# DAC_and_MIC.net
KiCad netlist of a schematic drawn in Altium Designer
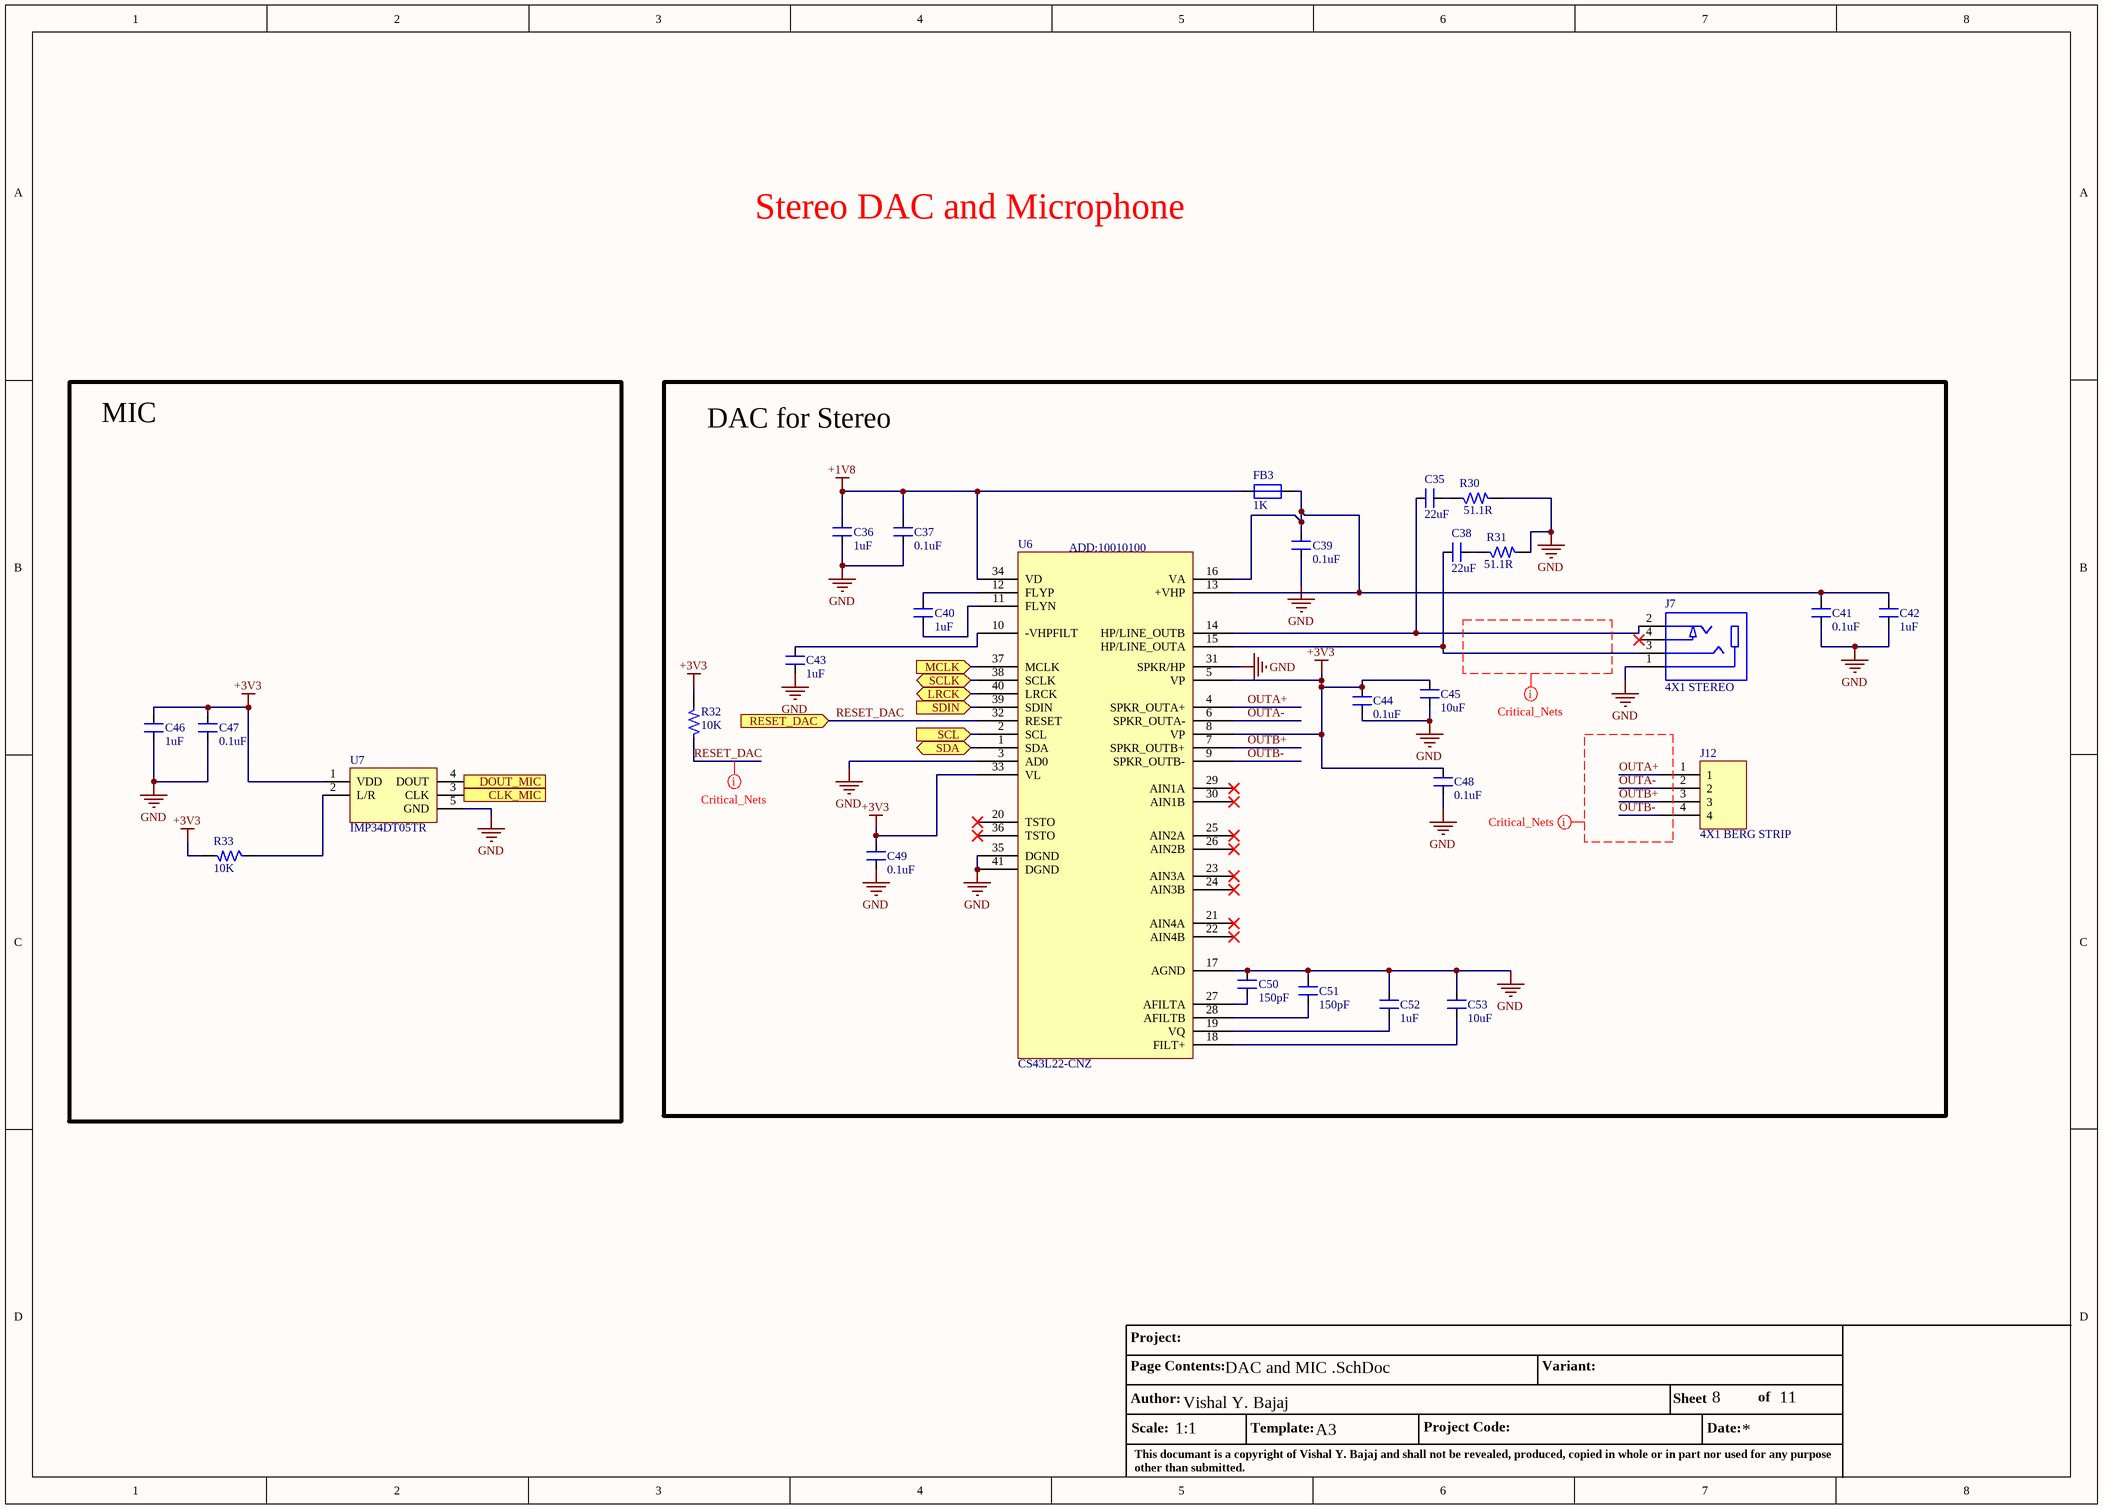
[diagram p0: DAC and MIC .SchDoc]

(export (version "E")
  (design (tool "Eeschema 10.0.6"))
  (components
    (comp (ref "C35")
      (value "22uF")
      (footprint "CAP_0805")
      (description "22µF ±20% 25V Ceramic Capacitor X5R 0805 (2012 Metric)")
      (fields
        (field (name "MANUFACTURER") "Murata")
        (field (name "MANUFACTURER PART NUMBER") "GRM21BR61E226ME44L")
      )
      (libsource (lib "ESTEEMPCBLIB") (part "CAP_22uF-25V-20%-0805"))
    )
    (comp (ref "C36")
      (value "1uF")
      (footprint "CAP_0805")
      (description "1µF ±5% 50V Ceramic Capacitor X7R 0805 (2012 Metric)")
      (fields
        (field (name "MANUFACTURER") "Samsung")
        (field (name "MANUFACTURER PART NUMBER") "CC0805JKX7R9BB105")
      )
      (libsource (lib "ESTEEMPCBLIB") (part "CAP_1uF-50V-5%-0805"))
    )
    (comp (ref "C37")
      (value "0.1uF")
      (footprint "CAP_0805")
      (description "0.1µF ±5% 50V Ceramic Capacitor X7R 0805 (2012 Metric)")
      (fields
        (field (name "MANUFACTURER") "AVX Corporation")
        (field (name "MANUFACTURER PART NUMBER") "08055C104JAT4A")
      )
      (libsource (lib "ESTEEMPCBLIB") (part "CAP_0.1uF-50V-5%-0805"))
    )
    (comp (ref "C38")
      (value "22uF")
      (footprint "CAP_0805")
      (description "22µF ±20% 25V Ceramic Capacitor X5R 0805 (2012 Metric)")
      (fields
        (field (name "MANUFACTURER") "Murata")
        (field (name "MANUFACTURER PART NUMBER") "GRM21BR61E226ME44L")
      )
      (libsource (lib "ESTEEMPCBLIB") (part "CAP_22uF-25V-20%-0805"))
    )
    (comp (ref "C39")
      (value "0.1uF")
      (footprint "CAP_0805")
      (description "0.1µF ±5% 50V Ceramic Capacitor X7R 0805 (2012 Metric)")
      (fields
        (field (name "MANUFACTURER") "AVX Corporation")
        (field (name "MANUFACTURER PART NUMBER") "08055C104JAT4A")
      )
      (libsource (lib "ESTEEMPCBLIB") (part "CAP_0.1uF-50V-5%-0805"))
    )
    (comp (ref "C40")
      (value "1uF")
      (footprint "CAP_0805")
      (description "1µF ±5% 50V Ceramic Capacitor X7R 0805 (2012 Metric)")
      (fields
        (field (name "MANUFACTURER") "Samsung")
        (field (name "MANUFACTURER PART NUMBER") "CC0805JKX7R9BB105")
      )
      (libsource (lib "ESTEEMPCBLIB") (part "CAP_1uF-50V-5%-0805"))
    )
    (comp (ref "C41")
      (value "0.1uF")
      (footprint "CAP_0805")
      (description "0.1µF ±5% 50V Ceramic Capacitor X7R 0805 (2012 Metric)")
      (fields
        (field (name "MANUFACTURER") "AVX Corporation")
        (field (name "MANUFACTURER PART NUMBER") "08055C104JAT4A")
      )
      (libsource (lib "ESTEEMPCBLIB") (part "CAP_0.1uF-50V-5%-0805"))
    )
    (comp (ref "C42")
      (value "1uF")
      (footprint "CAP_0805")
      (description "1µF ±5% 50V Ceramic Capacitor X7R 0805 (2012 Metric)")
      (fields
        (field (name "MANUFACTURER") "Samsung")
        (field (name "MANUFACTURER PART NUMBER") "CC0805JKX7R9BB105")
      )
      (libsource (lib "ESTEEMPCBLIB") (part "CAP_1uF-50V-5%-0805"))
    )
    (comp (ref "C43")
      (value "1uF")
      (footprint "CAP_0805")
      (description "1µF ±5% 50V Ceramic Capacitor X7R 0805 (2012 Metric)")
      (fields
        (field (name "MANUFACTURER") "Samsung")
        (field (name "MANUFACTURER PART NUMBER") "CC0805JKX7R9BB105")
      )
      (libsource (lib "ESTEEMPCBLIB") (part "CAP_1uF-50V-5%-0805"))
    )
    (comp (ref "C44")
      (value "0.1uF")
      (footprint "CAP_0805")
      (description "0.1µF ±5% 50V Ceramic Capacitor X7R 0805 (2012 Metric)")
      (fields
        (field (name "MANUFACTURER") "AVX Corporation")
        (field (name "MANUFACTURER PART NUMBER") "08055C104JAT4A")
      )
      (libsource (lib "ESTEEMPCBLIB") (part "CAP_0.1uF-50V-5%-0805"))
    )
    (comp (ref "C45")
      (value "10uF")
      (footprint "CAP_1206")
      (description "10µF ±10% 50V Ceramic Capacitor X7R 1206 (3216 Metric)")
      (fields
        (field (name "MANUFACTURER") "KEMET")
        (field (name "MANUFACTURER PART NUMBER") "CL31B106KBHNNNE")
      )
      (libsource (lib "ESTEEMPCBLIB") (part "CAP_10uF-50V-10%-1206"))
    )
    (comp (ref "C46")
      (value "1uF")
      (footprint "CAP_0805")
      (description "1µF ±5% 50V Ceramic Capacitor X7R 0805 (2012 Metric)")
      (fields
        (field (name "MANUFACTURER") "Samsung")
        (field (name "MANUFACTURER PART NUMBER") "CC0805JKX7R9BB105")
      )
      (libsource (lib "ESTEEMPCBLIB") (part "CAP_1uF-50V-5%-0805"))
    )
    (comp (ref "C47")
      (value "0.1uF")
      (footprint "CAP_0805")
      (description "0.1µF ±5% 50V Ceramic Capacitor X7R 0805 (2012 Metric)")
      (fields
        (field (name "MANUFACTURER") "AVX Corporation")
        (field (name "MANUFACTURER PART NUMBER") "08055C104JAT4A")
      )
      (libsource (lib "ESTEEMPCBLIB") (part "CAP_0.1uF-50V-5%-0805"))
    )
    (comp (ref "C48")
      (value "0.1uF")
      (footprint "CAP_0805")
      (description "0.1µF ±5% 50V Ceramic Capacitor X7R 0805 (2012 Metric)")
      (fields
        (field (name "MANUFACTURER") "AVX Corporation")
        (field (name "MANUFACTURER PART NUMBER") "08055C104JAT4A")
      )
      (libsource (lib "ESTEEMPCBLIB") (part "CAP_0.1uF-50V-5%-0805"))
    )
    (comp (ref "C49")
      (value "0.1uF")
      (footprint "CAP_0805")
      (description "0.1µF ±5% 50V Ceramic Capacitor X7R 0805 (2012 Metric)")
      (fields
        (field (name "MANUFACTURER") "AVX Corporation")
        (field (name "MANUFACTURER PART NUMBER") "08055C104JAT4A")
      )
      (libsource (lib "ESTEEMPCBLIB") (part "CAP_0.1uF-50V-5%-0805"))
    )
    (comp (ref "C50")
      (value "150pF")
      (footprint "CAP_0805")
      (description "150pF ±10% 50V Ceramic Capacitor C0G, NP0 0805 (2012 Metric)")
      (fields
        (field (name "MANUFACTURER") "AVX Corporation")
        (field (name "MANUFACTURER PART NUMBER") "08055A151KAT2A")
      )
      (libsource (lib "ESTEEMPCBLIB") (part "CAP_150pF-50V-10%-0805"))
    )
    (comp (ref "C51")
      (value "150pF")
      (footprint "CAP_0805")
      (description "150pF ±10% 50V Ceramic Capacitor C0G, NP0 0805 (2012 Metric)")
      (fields
        (field (name "MANUFACTURER") "AVX Corporation")
        (field (name "MANUFACTURER PART NUMBER") "08055A151KAT2A")
      )
      (libsource (lib "ESTEEMPCBLIB") (part "CAP_150pF-50V-10%-0805"))
    )
    (comp (ref "C52")
      (value "1uF")
      (footprint "CAP_0805")
      (description "1µF ±5% 50V Ceramic Capacitor X7R 0805 (2012 Metric)")
      (fields
        (field (name "MANUFACTURER") "Samsung")
        (field (name "MANUFACTURER PART NUMBER") "CC0805JKX7R9BB105")
      )
      (libsource (lib "ESTEEMPCBLIB") (part "CAP_1uF-50V-5%-0805"))
    )
    (comp (ref "C53")
      (value "10uF")
      (footprint "CAP_1206")
      (description "10µF ±10% 50V Ceramic Capacitor X7R 1206 (3216 Metric)")
      (fields
        (field (name "MANUFACTURER") "KEMET")
        (field (name "MANUFACTURER PART NUMBER") "CL31B106KBHNNNE")
      )
      (libsource (lib "ESTEEMPCBLIB") (part "CAP_10uF-50V-10%-1206"))
    )
    (comp (ref "FB3")
      (value "1K")
      (footprint "IND_0805")
      (description "1 kOhms @ 100MHz 1 Power Line Ferrite Bead 0805 (2012 Metric) 1.6A")
      (fields
        (field (name "MANUFACTURER") "Laird")
        (field (name "MANUFACTURER PART NUMBER") "BLM21SP102SH1D")
      )
      (libsource (lib "ESTEEMPCBLIB") (part "FB_1K-100MHZ-1.6A-0805"))
    )
    (comp (ref "J7")
      (value "4X1 STEREO")
      (footprint "CON_SJ-2504A-SMT-TR_SMD")
      (fields
        (field (name "MANUFACTURER") "CUI Devices")
        (field (name "MANUFACTURER PART NUMBER") "SJ-2504A-SMT-TR")
      )
      (libsource (lib "ESTEEMPCBLIB") (part "CON-PLG-STEREO_4X1-100-RA-SMD"))
    )
    (comp (ref "J12")
      (value "4X1 BERG STRIP")
      (footprint "CON4_100_40D72_TH_ST_MALE")
      (description "4 Pins, 1 Row 2.54mm Pitch, Straight bergstrip, Male")
      (fields (field (name "MANUFACTURER") "NA"))
      (libsource (lib "ESTEEMPCBLIB") (part "CON-BS-PLG_4X1-100-ST-TH"))
    )
    (comp (ref "R30")
      (value "51.1R")
      (footprint "RES_0603")
      (description "51.1 Ohms ±1% 0.1W, 1/10W Chip Resistor 0603 (1608 Metric) Thick Film")
      (fields
        (field (name "MANUFACTURER") "Vishay Dale")
        (field (name "MANUFACTURER PART NUMBER") "CRCW060351R1FKEAC")
      )
      (libsource (lib "ESTEEMPCBLIB") (part "RES_51.1R-0.1W-1%-0603"))
    )
    (comp (ref "R31")
      (value "51.1R")
      (footprint "RES_0603")
      (description "51.1 Ohms ±1% 0.1W, 1/10W Chip Resistor 0603 (1608 Metric) Thick Film")
      (fields
        (field (name "MANUFACTURER") "Vishay Dale")
        (field (name "MANUFACTURER PART NUMBER") "CRCW060351R1FKEAC")
      )
      (libsource (lib "ESTEEMPCBLIB") (part "RES_51.1R-0.1W-1%-0603"))
    )
    (comp (ref "R32")
      (value "10K")
      (footprint "RES_0805")
      (description "10 kOhms ±1% 0.125W, 1/8W Chip Resistor 0805 (2012 Metric) Automotive AEC-Q200 Thick Film")
      (fields (field (name "MANUFACTURER") "CTS") (field (name "MANUFACTURER PART NUMBER") "WR08X1002FTL"))
      (libsource (lib "ESTEEMPCBLIB") (part "RES_10K-0.125W-1%-0805"))
    )
    (comp (ref "R33")
      (value "10K")
      (footprint "RES_0805")
      (description "10 kOhms ±1% 0.125W, 1/8W Chip Resistor 0805 (2012 Metric) Automotive AEC-Q200 Thick Film")
      (fields (field (name "MANUFACTURER") "CTS") (field (name "MANUFACTURER PART NUMBER") "WR08X1002FTL"))
      (libsource (lib "ESTEEMPCBLIB") (part "RES_10K-0.125W-1%-0805"))
    )
    (comp (ref "U6")
      (value "CS43L22-CNZ")
      (footprint "QFN40_19_284_33X9_SMD")
      (description "Audio D/A Converter ICs Low Power Stereo DAC w/ClassD Spkr Driver")
      (fields (field (name "MANUFACTURER") "Cirrus Logic"))
      (libsource (lib "ESTEEMPCBLIB") (part "IC_CS43L22"))
    )
    (comp (ref "U7")
      (value "IMP34DT05TR")
      (footprint "HCLGA-4_53_137_15X37_SMD")
      (description "MEMS Microphones AUTO & INDUSTRIAL SENSORS")
      (fields (field (name "MANUFACTURER") "STMicroelectronics"))
      (libsource (lib "ESTEEMPCBLIB") (part "IC_IMP34DT05TR"))
    )
  )
  (nets
    (net (code "1") (name "+1V8") (class "Default")
      (node (ref "C36") (pin "2") (pinfunction "2_2") (pintype "passive"))
      (node (ref "C37") (pin "2") (pinfunction "2_2") (pintype "passive"))
      (node (ref "FB3") (pin "1") (pinfunction "1_1") (pintype "passive"))
      (node (ref "U6") (pin "34") (pinfunction "VD_34") (pintype "passive"))
    )
    (net (code "2") (name "+3V3") (class "Default")
      (node (ref "C44") (pin "2") (pinfunction "2_2") (pintype "passive"))
      (node (ref "C45") (pin "2") (pinfunction "2_2") (pintype "passive"))
      (node (ref "C46") (pin "2") (pinfunction "2_2") (pintype "passive"))
      (node (ref "C47") (pin "2") (pinfunction "2_2") (pintype "passive"))
      (node (ref "C48") (pin "2") (pinfunction "2_2") (pintype "passive"))
      (node (ref "C49") (pin "2") (pinfunction "2_2") (pintype "passive"))
      (node (ref "R32") (pin "2") (pinfunction "2_2") (pintype "passive"))
      (node (ref "R33") (pin "2") (pinfunction "2_2") (pintype "passive"))
      (node (ref "U6") (pin "33") (pinfunction "VL_33") (pintype "passive"))
      (node (ref "U6") (pin "5") (pinfunction "VP_5") (pintype "passive"))
      (node (ref "U6") (pin "8") (pinfunction "VP_8") (pintype "passive"))
      (node (ref "U7") (pin "1") (pinfunction "VDD_1") (pintype "passive"))
    )
    (net (code "3") (name "/CLK_MIC") (class "Default")
      (node (ref "U7") (pin "3") (pinfunction "CLK_3") (pintype "passive"))
    )
    (net (code "4") (name "/DOUT_MIC") (class "Default")
      (node (ref "U7") (pin "4") (pinfunction "DOUT_4") (pintype "passive"))
    )
    (net (code "5") (name "/LRCK") (class "Default")
      (node (ref "U6") (pin "40") (pinfunction "LRCK_40") (pintype "passive"))
    )
    (net (code "6") (name "/MCLK") (class "Default")
      (node (ref "U6") (pin "37") (pinfunction "MCLK_37") (pintype "passive"))
    )
    (net (code "7") (name "/OUTA+") (class "Default")
      (node (ref "J12") (pin "1") (pinfunction "1_1") (pintype "passive"))
      (node (ref "U6") (pin "4") (pinfunction "SPKR_OUTA+_4") (pintype "passive"))
    )
    (net (code "8") (name "/OUTA-") (class "Default")
      (node (ref "J12") (pin "2") (pinfunction "2_2") (pintype "passive"))
      (node (ref "U6") (pin "6") (pinfunction "SPKR_OUTA-_6") (pintype "passive"))
    )
    (net (code "9") (name "/OUTB+") (class "Default")
      (node (ref "J12") (pin "3") (pinfunction "3_3") (pintype "passive"))
      (node (ref "U6") (pin "7") (pinfunction "SPKR_OUTB+_7") (pintype "passive"))
    )
    (net (code "10") (name "/OUTB-") (class "Default")
      (node (ref "J12") (pin "4") (pinfunction "4_4") (pintype "passive"))
      (node (ref "U6") (pin "9") (pinfunction "SPKR_OUTB-_9") (pintype "passive"))
    )
    (net (code "11") (name "/RESET_DAC") (class "Default")
      (node (ref "R32") (pin "1") (pinfunction "1_1") (pintype "passive"))
      (node (ref "U6") (pin "32") (pinfunction "RESET_32") (pintype "passive"))
    )
    (net (code "12") (name "/SCL") (class "Default")
      (node (ref "U6") (pin "2") (pinfunction "SCL_2") (pintype "passive"))
    )
    (net (code "13") (name "/SCLK") (class "Default")
      (node (ref "U6") (pin "38") (pinfunction "SCLK_38") (pintype "passive"))
    )
    (net (code "14") (name "/SDA") (class "Default")
      (node (ref "U6") (pin "1") (pinfunction "SDA_1") (pintype "passive"))
    )
    (net (code "15") (name "/SDIN") (class "Default")
      (node (ref "U6") (pin "39") (pinfunction "SDIN_39") (pintype "passive"))
    )
    (net (code "16") (name "GND") (class "Default")
      (node (ref "C36") (pin "1") (pinfunction "1_1") (pintype "passive"))
      (node (ref "C37") (pin "1") (pinfunction "1_1") (pintype "passive"))
      (node (ref "C39") (pin "1") (pinfunction "1_1") (pintype "passive"))
      (node (ref "C41") (pin "1") (pinfunction "1_1") (pintype "passive"))
      (node (ref "C42") (pin "1") (pinfunction "1_1") (pintype "passive"))
      (node (ref "C43") (pin "1") (pinfunction "1_1") (pintype "passive"))
      (node (ref "C44") (pin "1") (pinfunction "1_1") (pintype "passive"))
      (node (ref "C45") (pin "1") (pinfunction "1_1") (pintype "passive"))
      (node (ref "C46") (pin "1") (pinfunction "1_1") (pintype "passive"))
      (node (ref "C47") (pin "1") (pinfunction "1_1") (pintype "passive"))
      (node (ref "C48") (pin "1") (pinfunction "1_1") (pintype "passive"))
      (node (ref "C49") (pin "1") (pinfunction "1_1") (pintype "passive"))
      (node (ref "C50") (pin "2") (pinfunction "2_2") (pintype "passive"))
      (node (ref "C51") (pin "2") (pinfunction "2_2") (pintype "passive"))
      (node (ref "C52") (pin "2") (pinfunction "2_2") (pintype "passive"))
      (node (ref "C53") (pin "2") (pinfunction "2_2") (pintype "passive"))
      (node (ref "J7") (pin "1") (pinfunction "1_1") (pintype "passive"))
      (node (ref "R30") (pin "2") (pinfunction "2_2") (pintype "passive"))
      (node (ref "R31") (pin "2") (pinfunction "2_2") (pintype "passive"))
      (node (ref "U6") (pin "17") (pinfunction "AGND_17") (pintype "passive"))
      (node (ref "U6") (pin "3") (pinfunction "AD0_3") (pintype "passive"))
      (node (ref "U6") (pin "31") (pinfunction "SPKR/HP_31") (pintype "passive"))
      (node (ref "U6") (pin "35") (pinfunction "DGND_35") (pintype "passive"))
      (node (ref "U6") (pin "41") (pinfunction "DGND_41") (pintype "passive"))
      (node (ref "U7") (pin "5") (pinfunction "GND_5") (pintype "passive"))
    )
    (net (code "17") (name "Net-(C35-Pad2)") (class "Default")
      (node (ref "C35") (pin "2") (pinfunction "2_2") (pintype "passive"))
      (node (ref "R30") (pin "1") (pinfunction "1_1") (pintype "passive"))
    )
    (net (code "18") (name "Net-(C38-Pad2)") (class "Default")
      (node (ref "C38") (pin "2") (pinfunction "2_2") (pintype "passive"))
      (node (ref "R31") (pin "1") (pinfunction "1_1") (pintype "passive"))
    )
    (net (code "19") (name "Net-(U6-+VHP)") (class "Default")
      (node (ref "C39") (pin "2") (pinfunction "2_2") (pintype "passive"))
      (node (ref "C41") (pin "2") (pinfunction "2_2") (pintype "passive"))
      (node (ref "C42") (pin "2") (pinfunction "2_2") (pintype "passive"))
      (node (ref "FB3") (pin "2") (pinfunction "2_2") (pintype "passive"))
      (node (ref "U6") (pin "13") (pinfunction "+VHP_13") (pintype "passive"))
      (node (ref "U6") (pin "16") (pinfunction "VA_16") (pintype "passive"))
    )
    (net (code "20") (name "Net-(U6--VHPFILT)") (class "Default")
      (node (ref "C43") (pin "2") (pinfunction "2_2") (pintype "passive"))
      (node (ref "U6") (pin "10") (pinfunction "-VHPFILT_10") (pintype "passive"))
    )
    (net (code "21") (name "Net-(U6-AFILTA)") (class "Default")
      (node (ref "C50") (pin "1") (pinfunction "1_1") (pintype "passive"))
      (node (ref "U6") (pin "27") (pinfunction "AFILTA_27") (pintype "passive"))
    )
    (net (code "22") (name "Net-(U6-AFILTB)") (class "Default")
      (node (ref "C51") (pin "1") (pinfunction "1_1") (pintype "passive"))
      (node (ref "U6") (pin "28") (pinfunction "AFILTB_28") (pintype "passive"))
    )
    (net (code "23") (name "Net-(U6-FILT+)") (class "Default")
      (node (ref "C53") (pin "1") (pinfunction "1_1") (pintype "passive"))
      (node (ref "U6") (pin "18") (pinfunction "FILT+_18") (pintype "passive"))
    )
    (net (code "24") (name "Net-(U6-FLYN)") (class "Default")
      (node (ref "C40") (pin "1") (pinfunction "1_1") (pintype "passive"))
      (node (ref "U6") (pin "11") (pinfunction "FLYN_11") (pintype "passive"))
    )
    (net (code "25") (name "Net-(U6-FLYP)") (class "Default")
      (node (ref "C40") (pin "2") (pinfunction "2_2") (pintype "passive"))
      (node (ref "U6") (pin "12") (pinfunction "FLYP_12") (pintype "passive"))
    )
    (net (code "26") (name "Net-(U6-HP{slash}LINE_OUTA)") (class "Default")
      (node (ref "C38") (pin "1") (pinfunction "1_1") (pintype "passive"))
      (node (ref "J7") (pin "3") (pinfunction "3_3") (pintype "passive"))
      (node (ref "U6") (pin "15") (pinfunction "HP/LINE_OUTA_15") (pintype "passive"))
    )
    (net (code "27") (name "Net-(U6-HP{slash}LINE_OUTB)") (class "Default")
      (node (ref "C35") (pin "1") (pinfunction "1_1") (pintype "passive"))
      (node (ref "J7") (pin "2") (pinfunction "2_2") (pintype "passive"))
      (node (ref "U6") (pin "14") (pinfunction "HP/LINE_OUTB_14") (pintype "passive"))
    )
    (net (code "28") (name "Net-(U6-VQ)") (class "Default")
      (node (ref "C52") (pin "1") (pinfunction "1_1") (pintype "passive"))
      (node (ref "U6") (pin "19") (pinfunction "VQ_19") (pintype "passive"))
    )
    (net (code "29") (name "Net-(U7-L{slash}R)") (class "Default")
      (node (ref "R33") (pin "1") (pinfunction "1_1") (pintype "passive"))
      (node (ref "U7") (pin "2") (pinfunction "L/R_2") (pintype "passive"))
    )
    (net (code "30") (name "unconnected-(J7-Pad4)") (class "Default")
      (node (ref "J7") (pin "4") (pinfunction "4_4") (pintype "passive+no_connect"))
    )
    (net (code "31") (name "unconnected-(U6-AIN1A-Pad29)") (class "Default")
      (node (ref "U6") (pin "29") (pinfunction "AIN1A_29") (pintype "passive+no_connect"))
    )
    (net (code "32") (name "unconnected-(U6-AIN1B-Pad30)") (class "Default")
      (node (ref "U6") (pin "30") (pinfunction "AIN1B_30") (pintype "passive+no_connect"))
    )
    (net (code "33") (name "unconnected-(U6-AIN2A-Pad25)") (class "Default")
      (node (ref "U6") (pin "25") (pinfunction "AIN2A_25") (pintype "passive+no_connect"))
    )
    (net (code "34") (name "unconnected-(U6-AIN2B-Pad26)") (class "Default")
      (node (ref "U6") (pin "26") (pinfunction "AIN2B_26") (pintype "passive+no_connect"))
    )
    (net (code "35") (name "unconnected-(U6-AIN3A-Pad23)") (class "Default")
      (node (ref "U6") (pin "23") (pinfunction "AIN3A_23") (pintype "passive+no_connect"))
    )
    (net (code "36") (name "unconnected-(U6-AIN3B-Pad24)") (class "Default")
      (node (ref "U6") (pin "24") (pinfunction "AIN3B_24") (pintype "passive+no_connect"))
    )
    (net (code "37") (name "unconnected-(U6-AIN4A-Pad21)") (class "Default")
      (node (ref "U6") (pin "21") (pinfunction "AIN4A_21") (pintype "passive+no_connect"))
    )
    (net (code "38") (name "unconnected-(U6-AIN4B-Pad22)") (class "Default")
      (node (ref "U6") (pin "22") (pinfunction "AIN4B_22") (pintype "passive+no_connect"))
    )
    (net (code "39") (name "unconnected-(U6-TSTO-Pad20)") (class "Default")
      (node (ref "U6") (pin "20") (pinfunction "TSTO_20") (pintype "passive+no_connect"))
    )
    (net (code "40") (name "unconnected-(U6-TSTO-Pad36)") (class "Default")
      (node (ref "U6") (pin "36") (pinfunction "TSTO_36") (pintype "passive+no_connect"))
    )
  )
)
